# 14_CPU_2.net
KiCad netlist of a schematic drawn in Altium Designer
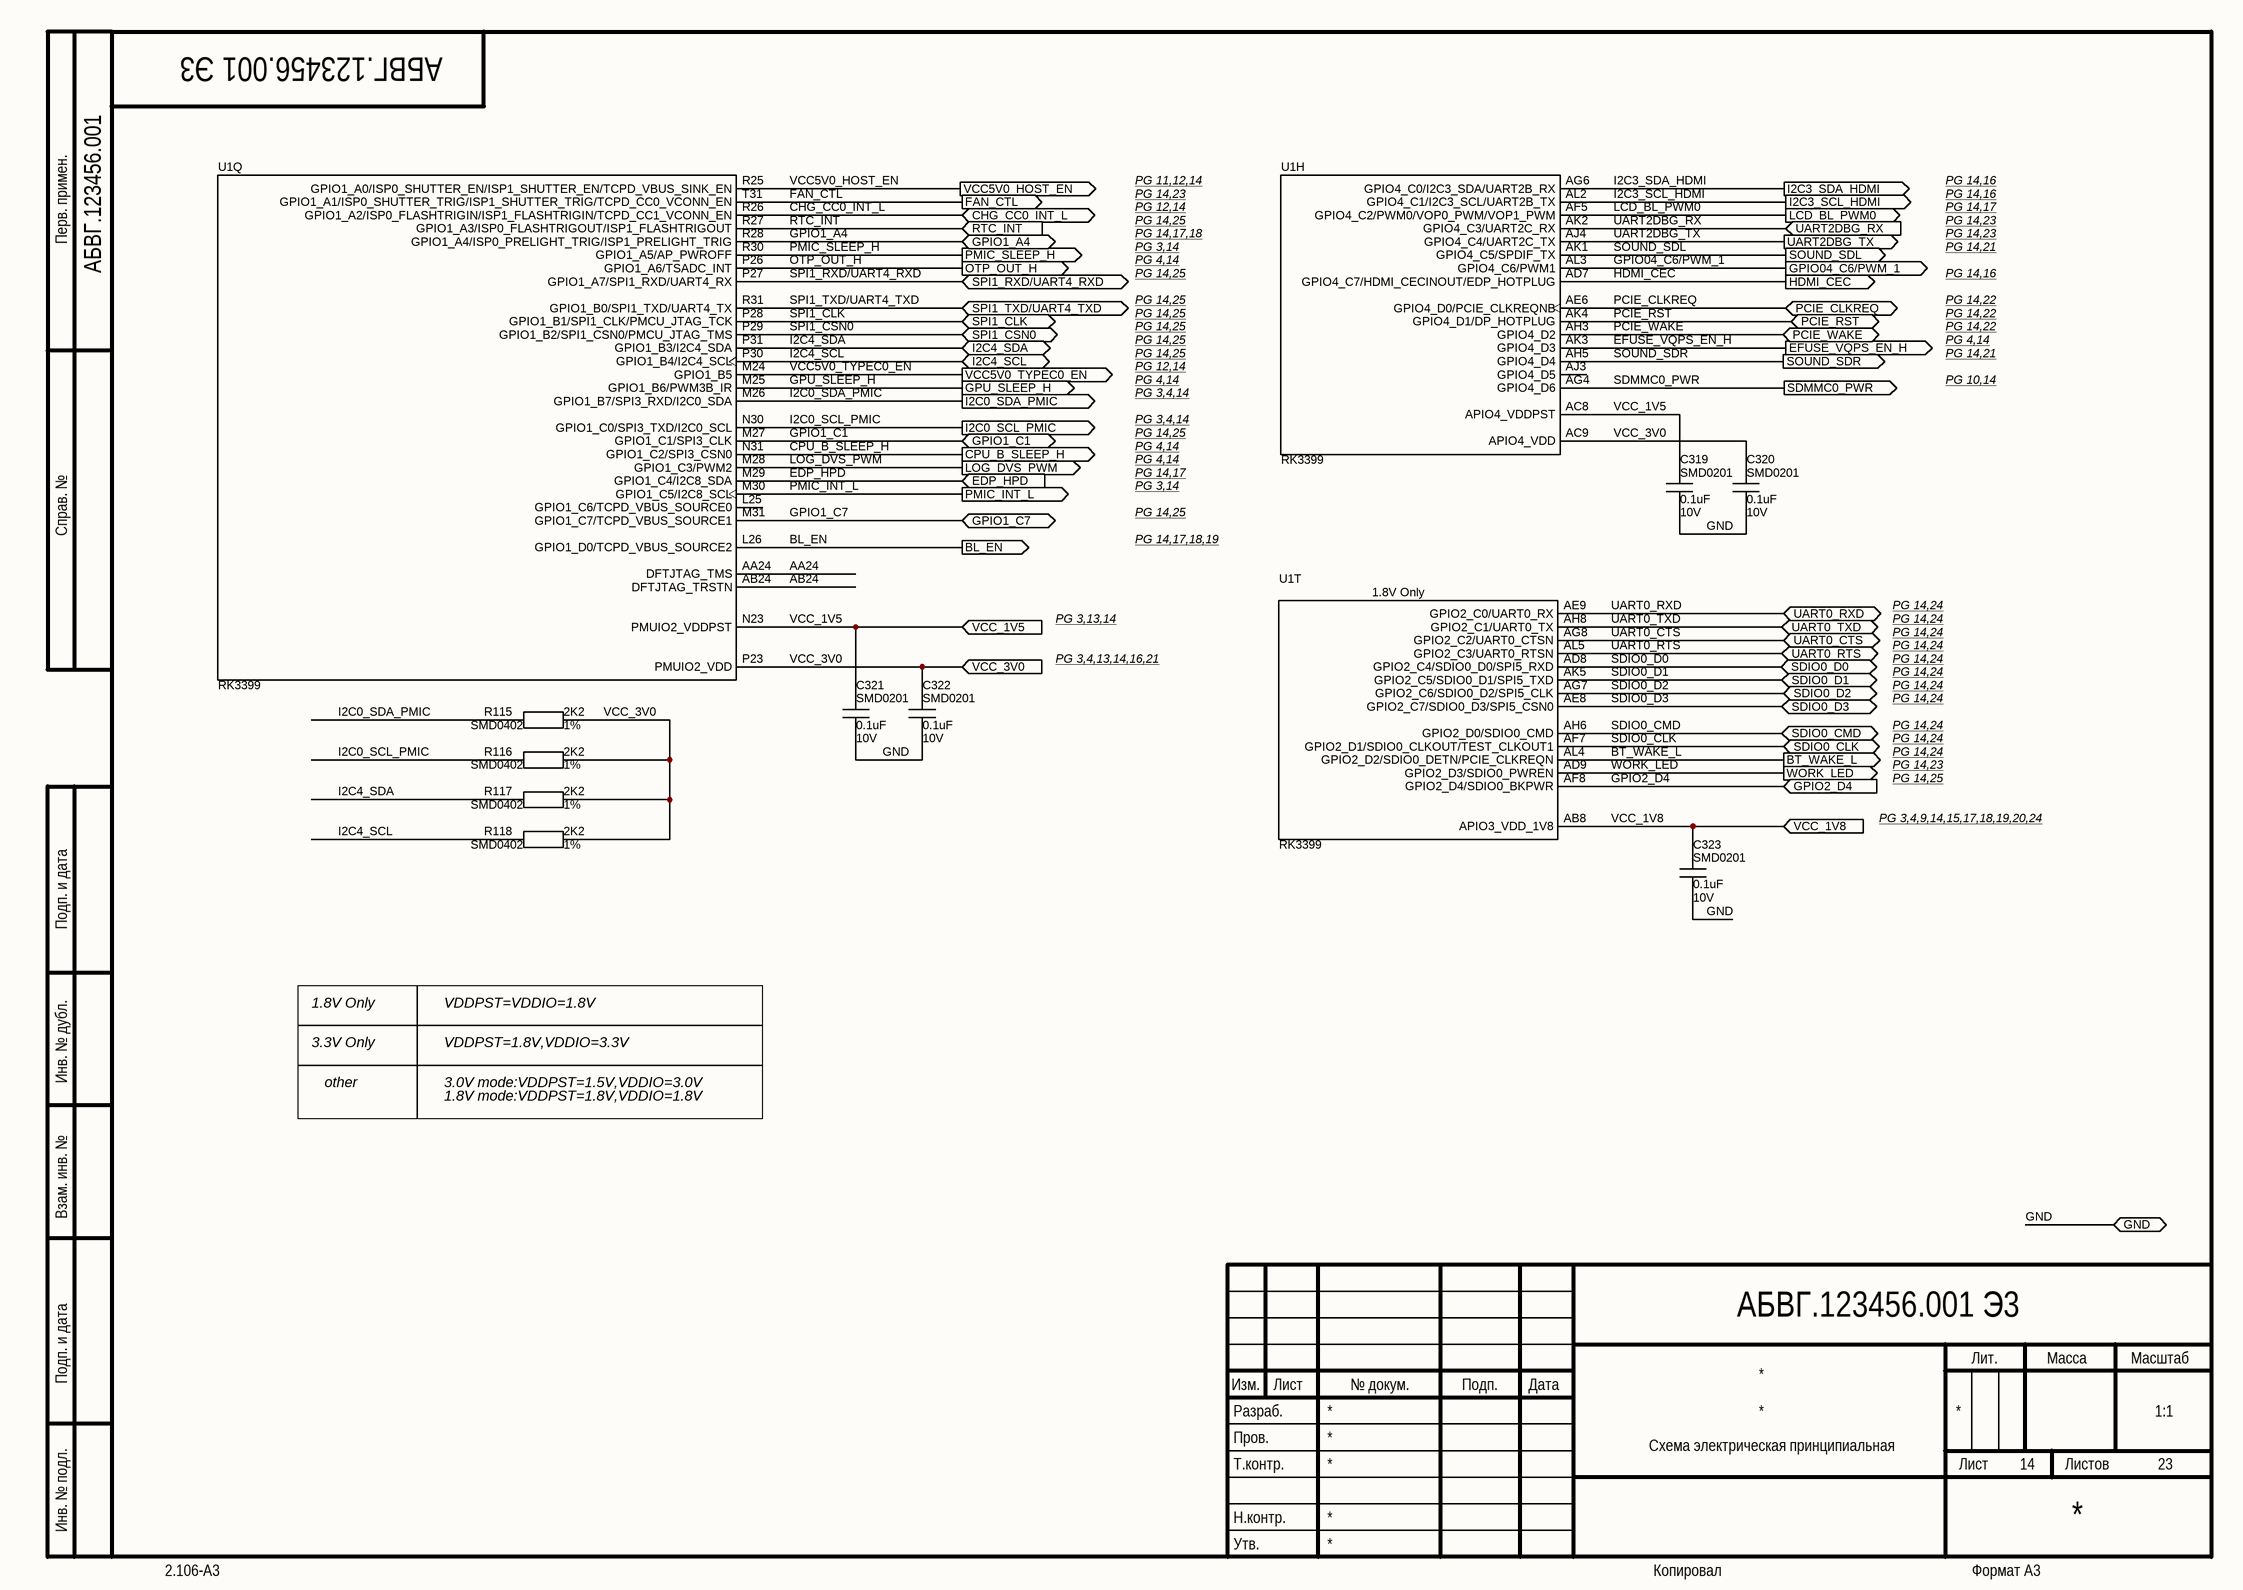
[diagram p0: 14 CPU_2.SchDoc]

(export (version "E")
  (design (tool "Eeschema 10.0.6"))
  (components
    (comp (ref "C319")
      (value "0.1uF")
      (footprint "Didur_PcbLib_1:CAP_SMD_0201")
      (fields
        (field (name "PACKAGE") "SMD0201")
        (field (name "PARTNUMBER") "CC0201KRX5R6BB104")
        (field (name "VOLTAGE") "10V")
      )
      (libsource (lib "Didur_SchLib_1") (part "Ceramic_Cap"))
    )
    (comp (ref "C320")
      (value "0.1uF")
      (footprint "Didur_PcbLib_1:CAP_SMD_0201")
      (fields
        (field (name "PACKAGE") "SMD0201")
        (field (name "PARTNUMBER") "CC0201KRX5R6BB104")
        (field (name "VOLTAGE") "10V")
      )
      (libsource (lib "Didur_SchLib_1") (part "Ceramic_Cap"))
    )
    (comp (ref "C321")
      (value "0.1uF")
      (footprint "Didur_PcbLib_1:CAP_SMD_0201")
      (fields
        (field (name "PACKAGE") "SMD0201")
        (field (name "PARTNUMBER") "CC0201KRX5R6BB104")
        (field (name "VOLTAGE") "10V")
      )
      (libsource (lib "Didur_SchLib_1") (part "Ceramic_Cap"))
    )
    (comp (ref "C322")
      (value "0.1uF")
      (footprint "Didur_PcbLib_1:CAP_SMD_0201")
      (fields
        (field (name "PACKAGE") "SMD0201")
        (field (name "PARTNUMBER") "CC0201KRX5R6BB104")
        (field (name "VOLTAGE") "10V")
      )
      (libsource (lib "Didur_SchLib_1") (part "Ceramic_Cap"))
    )
    (comp (ref "C323")
      (value "0.1uF")
      (footprint "Didur_PcbLib_1:CAP_SMD_0201")
      (fields
        (field (name "PACKAGE") "SMD0201")
        (field (name "PARTNUMBER") "CC0201KRX5R6BB104")
        (field (name "VOLTAGE") "10V")
      )
      (libsource (lib "Didur_SchLib_1") (part "Ceramic_Cap"))
    )
    (comp (ref "R115")
      (value "2K2")
      (footprint "Didur_PcbLib_1:RES_SMD_0402")
      (fields
        (field (name "PACKAGE") "SMD0402")
        (field (name "PARTNUMBER") "RC0402FR-072K2L")
        (field (name "TOLERANCE") "1%")
      )
      (libsource (lib "Didur_SchLib_1") (part "Chip_Res"))
    )
    (comp (ref "R116")
      (value "2K2")
      (footprint "Didur_PcbLib_1:RES_SMD_0402")
      (fields
        (field (name "PACKAGE") "SMD0402")
        (field (name "PARTNUMBER") "RC0402FR-072K2L")
        (field (name "TOLERANCE") "1%")
      )
      (libsource (lib "Didur_SchLib_1") (part "Chip_Res"))
    )
    (comp (ref "R117")
      (value "2K2")
      (footprint "Didur_PcbLib_1:RES_SMD_0402")
      (fields
        (field (name "PACKAGE") "SMD0402")
        (field (name "PARTNUMBER") "RC0402FR-072K2L")
        (field (name "TOLERANCE") "1%")
      )
      (libsource (lib "Didur_SchLib_1") (part "Chip_Res"))
    )
    (comp (ref "R118")
      (value "2K2")
      (footprint "Didur_PcbLib_1:RES_SMD_0402")
      (fields
        (field (name "PACKAGE") "SMD0402")
        (field (name "PARTNUMBER") "RC0402FR-072K2L")
        (field (name "TOLERANCE") "1%")
      )
      (libsource (lib "Didur_SchLib_1") (part "Chip_Res"))
    )
    (comp (ref "U1")
      (value "RK3399")
      (footprint "BGA828C65P31X31_2100X2100X161N")
      (fields (field (name "Comment") "RK3399_FF"))
      (libsource (lib "Didur_SchLib_1") (part "RK3399_FF"))
    )
  )
  (nets
    (net (code "1") (name "/AA24") (class "Default")
      (node (ref "U1") (pin "AA24") (pinfunction "DFTJTAG_TMS_AA24") (pintype "passive"))
    )
    (net (code "2") (name "/AB24") (class "Default")
      (node (ref "U1") (pin "AB24") (pinfunction "DFTJTAG_TRSTN_AB24") (pintype "passive"))
    )
    (net (code "3") (name "/BL_EN") (class "Default")
      (node (ref "U1") (pin "L26") (pinfunction "GPIO1_D0/TCPD_VBUS_SOURCE2_L26") (pintype "passive"))
    )
    (net (code "4") (name "/BT_WAKE_L") (class "Default")
      (node (ref "U1") (pin "AL4") (pinfunction "GPIO2_D2/SDIO0_DETN/PCIE_CLKREQN_AL4") (pintype "passive"))
    )
    (net (code "5") (name "/CHG_CC0_INT_L") (class "Default")
      (node (ref "U1") (pin "R26") (pinfunction "GPIO1_A2/ISP0_FLASHTRIGIN/ISP1_FLASHTRIGIN/TCPD_CC1_VCONN_EN_R26") (pintype "passive"))
    )
    (net (code "6") (name "/CPU_B_SLEEP_H") (class "Default")
      (node (ref "U1") (pin "N31") (pinfunction "GPIO1_C2/SPI3_CSN0_N31") (pintype "passive"))
    )
    (net (code "7") (name "/EDP_HPD") (class "Default")
      (node (ref "U1") (pin "M29") (pinfunction "GPIO1_C4/I2C8_SDA_M29") (pintype "passive"))
    )
    (net (code "8") (name "/EFUSE_VQPS_EN_H") (class "Default")
      (node (ref "U1") (pin "AK3") (pinfunction "GPIO4_D3_AK3") (pintype "passive"))
    )
    (net (code "9") (name "/FAN_CTL") (class "Default")
      (node (ref "U1") (pin "T31") (pinfunction "GPIO1_A1/ISP0_SHUTTER_TRIG/ISP1_SHUTTER_TRIG/TCPD_CC0_VCONN_EN_T31") (pintype "passive"))
    )
    (net (code "10") (name "/GND") (class "Default")
      (node (ref "C319") (pin "2") (pinfunction "2_2") (pintype "power_in"))
      (node (ref "C320") (pin "2") (pinfunction "2_2") (pintype "power_in"))
      (node (ref "C321") (pin "2") (pinfunction "2_2") (pintype "power_in"))
      (node (ref "C322") (pin "2") (pinfunction "2_2") (pintype "power_in"))
      (node (ref "C323") (pin "2") (pinfunction "2_2") (pintype "power_in"))
    )
    (net (code "11") (name "/GPIO1_A4") (class "Default")
      (node (ref "U1") (pin "R28") (pinfunction "GPIO1_A4/ISP0_PRELIGHT_TRIG/ISP1_PRELIGHT_TRIG_R28") (pintype "passive"))
    )
    (net (code "12") (name "/GPIO1_C1") (class "Default")
      (node (ref "U1") (pin "M27") (pinfunction "GPIO1_C1/SPI3_CLK_M27") (pintype "passive"))
    )
    (net (code "13") (name "/GPIO1_C7") (class "Default")
      (node (ref "U1") (pin "M31") (pinfunction "GPIO1_C7/TCPD_VBUS_SOURCE1_M31") (pintype "passive"))
    )
    (net (code "14") (name "/GPIO2_D4") (class "Default")
      (node (ref "U1") (pin "AF8") (pinfunction "GPIO2_D4/SDIO0_BKPWR_AF8") (pintype "passive"))
    )
    (net (code "15") (name "/GPIO04_C6{slash}PWM_1") (class "Default")
      (node (ref "U1") (pin "AL3") (pinfunction "GPIO4_C6/PWM1_AL3") (pintype "passive"))
    )
    (net (code "16") (name "/GPU_SLEEP_H") (class "Default")
      (node (ref "U1") (pin "M25") (pinfunction "GPIO1_B6/PWM3B_IR_M25") (pintype "passive"))
    )
    (net (code "17") (name "/HDMI_CEC") (class "Default")
      (node (ref "U1") (pin "AD7") (pinfunction "GPIO4_C7/HDMI_CECINOUT/EDP_HOTPLUG_AD7") (pintype "passive"))
    )
    (net (code "18") (name "/I2C0_SCL_PMIC") (class "Default")
      (node (ref "R116") (pin "2") (pinfunction "2_2") (pintype "passive"))
      (node (ref "U1") (pin "N30") (pinfunction "GPIO1_C0/SPI3_TXD/I2C0_SCL_N30") (pintype "passive"))
    )
    (net (code "19") (name "/I2C0_SDA_PMIC") (class "Default")
      (node (ref "R115") (pin "2") (pinfunction "2_2") (pintype "passive"))
      (node (ref "U1") (pin "M26") (pinfunction "GPIO1_B7/SPI3_RXD/I2C0_SDA_M26") (pintype "passive"))
    )
    (net (code "20") (name "/I2C3_SCL_HDMI") (class "Default")
      (node (ref "U1") (pin "AL2") (pinfunction "GPIO4_C1/I2C3_SCL/UART2B_TX_AL2") (pintype "passive"))
    )
    (net (code "21") (name "/I2C3_SDA_HDMI") (class "Default")
      (node (ref "U1") (pin "AG6") (pinfunction "GPIO4_C0/I2C3_SDA/UART2B_RX_AG6") (pintype "passive"))
    )
    (net (code "22") (name "/I2C4_SCL") (class "Default")
      (node (ref "R118") (pin "2") (pinfunction "2_2") (pintype "passive"))
      (node (ref "U1") (pin "P30") (pinfunction "GPIO1_B4/I2C4_SCL_P30") (pintype "passive"))
    )
    (net (code "23") (name "/I2C4_SDA") (class "Default")
      (node (ref "R117") (pin "2") (pinfunction "2_2") (pintype "passive"))
      (node (ref "U1") (pin "P31") (pinfunction "GPIO1_B3/I2C4_SDA_P31") (pintype "passive"))
    )
    (net (code "24") (name "/LCD_BL_PWM0") (class "Default")
      (node (ref "U1") (pin "AF5") (pinfunction "GPIO4_C2/PWM0/VOP0_PWM/VOP1_PWM_AF5") (pintype "passive"))
    )
    (net (code "25") (name "/LOG_DVS_PWM") (class "Default")
      (node (ref "U1") (pin "M28") (pinfunction "GPIO1_C3/PWM2_M28") (pintype "passive"))
    )
    (net (code "26") (name "/OTP_OUT_H") (class "Default")
      (node (ref "U1") (pin "P26") (pinfunction "GPIO1_A6/TSADC_INT_P26") (pintype "passive"))
    )
    (net (code "27") (name "/PCIE_CLKREQ") (class "Default")
      (node (ref "U1") (pin "AE6") (pinfunction "GPIO4_D0/PCIE_CLKREQNB_AE6") (pintype "passive"))
    )
    (net (code "28") (name "/PCIE_RST") (class "Default")
      (node (ref "U1") (pin "AK4") (pinfunction "GPIO4_D1/DP_HOTPLUG_AK4") (pintype "passive"))
    )
    (net (code "29") (name "/PCIE_WAKE") (class "Default")
      (node (ref "U1") (pin "AH3") (pinfunction "GPIO4_D2_AH3") (pintype "passive"))
    )
    (net (code "30") (name "/PMIC_INT_L") (class "Default")
      (node (ref "U1") (pin "M30") (pinfunction "GPIO1_C5/I2C8_SCL_M30") (pintype "passive"))
    )
    (net (code "31") (name "/PMIC_SLEEP_H") (class "Default")
      (node (ref "U1") (pin "R30") (pinfunction "GPIO1_A5/AP_PWROFF_R30") (pintype "passive"))
    )
    (net (code "32") (name "/RTC_INT") (class "Default")
      (node (ref "U1") (pin "R27") (pinfunction "GPIO1_A3/ISP0_FLASHTRIGOUT/ISP1_FLASHTRIGOUT_R27") (pintype "passive"))
    )
    (net (code "33") (name "/SDIO0_CLK") (class "Default")
      (node (ref "U1") (pin "AF7") (pinfunction "GPIO2_D1/SDIO0_CLKOUT/TEST_CLKOUT1_AF7") (pintype "passive"))
    )
    (net (code "34") (name "/SDIO0_CMD") (class "Default")
      (node (ref "U1") (pin "AH6") (pinfunction "GPIO2_D0/SDIO0_CMD_AH6") (pintype "passive"))
    )
    (net (code "35") (name "/SDIO0_D0") (class "Default")
      (node (ref "U1") (pin "AD8") (pinfunction "GPIO2_C4/SDIO0_D0/SPI5_RXD_AD8") (pintype "passive"))
    )
    (net (code "36") (name "/SDIO0_D1") (class "Default")
      (node (ref "U1") (pin "AK5") (pinfunction "GPIO2_C5/SDIO0_D1/SPI5_TXD_AK5") (pintype "passive"))
    )
    (net (code "37") (name "/SDIO0_D2") (class "Default")
      (node (ref "U1") (pin "AG7") (pinfunction "GPIO2_C6/SDIO0_D2/SPI5_CLK_AG7") (pintype "passive"))
    )
    (net (code "38") (name "/SDIO0_D3") (class "Default")
      (node (ref "U1") (pin "AE8") (pinfunction "GPIO2_C7/SDIO0_D3/SPI5_CSN0_AE8") (pintype "passive"))
    )
    (net (code "39") (name "/SDMMC0_PWR") (class "Default")
      (node (ref "U1") (pin "AG4") (pinfunction "GPIO4_D6_AG4") (pintype "passive"))
    )
    (net (code "40") (name "/SOUND_SDL") (class "Default")
      (node (ref "U1") (pin "AK1") (pinfunction "GPIO4_C5/SPDIF_TX_AK1") (pintype "passive"))
    )
    (net (code "41") (name "/SOUND_SDR") (class "Default")
      (node (ref "U1") (pin "AH5") (pinfunction "GPIO4_D4_AH5") (pintype "passive"))
    )
    (net (code "42") (name "/SPI1_CLK") (class "Default")
      (node (ref "U1") (pin "P28") (pinfunction "GPIO1_B1/SPI1_CLK/PMCU_JTAG_TCK_P28") (pintype "passive"))
    )
    (net (code "43") (name "/SPI1_CSN0") (class "Default")
      (node (ref "U1") (pin "P29") (pinfunction "GPIO1_B2/SPI1_CSN0/PMCU_JTAG_TMS_P29") (pintype "passive"))
    )
    (net (code "44") (name "/SPI1_RXD{slash}UART4_RXD") (class "Default")
      (node (ref "U1") (pin "P27") (pinfunction "GPIO1_A7/SPI1_RXD/UART4_RX_P27") (pintype "passive"))
    )
    (net (code "45") (name "/SPI1_TXD{slash}UART4_TXD") (class "Default")
      (node (ref "U1") (pin "R31") (pinfunction "GPIO1_B0/SPI1_TXD/UART4_TX_R31") (pintype "passive"))
    )
    (net (code "46") (name "/UART0_CTS") (class "Default")
      (node (ref "U1") (pin "AG8") (pinfunction "GPIO2_C2/UART0_CTSN_AG8") (pintype "passive"))
    )
    (net (code "47") (name "/UART0_RTS") (class "Default")
      (node (ref "U1") (pin "AL5") (pinfunction "GPIO2_C3/UART0_RTSN_AL5") (pintype "passive"))
    )
    (net (code "48") (name "/UART0_RXD") (class "Default")
      (node (ref "U1") (pin "AE9") (pinfunction "GPIO2_C0/UART0_RX_AE9") (pintype "passive"))
    )
    (net (code "49") (name "/UART0_TXD") (class "Default")
      (node (ref "U1") (pin "AH8") (pinfunction "GPIO2_C1/UART0_TX_AH8") (pintype "passive"))
    )
    (net (code "50") (name "/UART2DBG_RX") (class "Default")
      (node (ref "U1") (pin "AK2") (pinfunction "GPIO4_C3/UART2C_RX_AK2") (pintype "passive"))
    )
    (net (code "51") (name "/UART2DBG_TX") (class "Default")
      (node (ref "U1") (pin "AJ4") (pinfunction "GPIO4_C4/UART2C_TX_AJ4") (pintype "passive"))
    )
    (net (code "52") (name "/VCC5V0_HOST_EN") (class "Default")
      (node (ref "U1") (pin "R25") (pinfunction "GPIO1_A0/ISP0_SHUTTER_EN/ISP1_SHUTTER_EN/TCPD_VBUS_SINK_EN_R25") (pintype "passive"))
    )
    (net (code "53") (name "/VCC5V0_TYPEC0_EN") (class "Default")
      (node (ref "U1") (pin "M24") (pinfunction "GPIO1_B5_M24") (pintype "passive"))
    )
    (net (code "54") (name "/VCC_1V5") (class "Default")
      (node (ref "C319") (pin "1") (pinfunction "1_1") (pintype "power_in"))
      (node (ref "C321") (pin "1") (pinfunction "1_1") (pintype "power_in"))
      (node (ref "U1") (pin "AC8") (pinfunction "APIO4_VDDPST_AC8") (pintype "passive"))
      (node (ref "U1") (pin "N23") (pinfunction "PMUIO2_VDDPST_N23") (pintype "passive"))
    )
    (net (code "55") (name "/VCC_1V8") (class "Default")
      (node (ref "C323") (pin "1") (pinfunction "1_1") (pintype "power_in"))
      (node (ref "U1") (pin "AB8") (pinfunction "APIO3_VDD_1V8_AB8") (pintype "passive"))
    )
    (net (code "56") (name "/VCC_3V0") (class "Default")
      (node (ref "C320") (pin "1") (pinfunction "1_1") (pintype "power_in"))
      (node (ref "C322") (pin "1") (pinfunction "1_1") (pintype "power_in"))
      (node (ref "R115") (pin "1") (pinfunction "1_1") (pintype "passive"))
      (node (ref "R116") (pin "1") (pinfunction "1_1") (pintype "passive"))
      (node (ref "R117") (pin "1") (pinfunction "1_1") (pintype "passive"))
      (node (ref "R118") (pin "1") (pinfunction "1_1") (pintype "passive"))
      (node (ref "U1") (pin "AC9") (pinfunction "APIO4_VDD_AC9") (pintype "passive"))
      (node (ref "U1") (pin "P23") (pinfunction "PMUIO2_VDD_P23") (pintype "passive"))
    )
    (net (code "57") (name "/WORK_LED") (class "Default")
      (node (ref "U1") (pin "AD9") (pinfunction "GPIO2_D3/SDIO0_PWREN_AD9") (pintype "passive"))
    )
    (net (code "58") (name "unconnected-(U1H-GPIO4_D5-PadAJ3)") (class "Default")
      (node (ref "U1") (pin "AJ3") (pinfunction "GPIO4_D5_AJ3") (pintype "passive"))
    )
    (net (code "59") (name "unconnected-(U1Q-GPIO1_C6{slash}TCPD_VBUS_SOURCE0-PadL25)") (class "Default")
      (node (ref "U1") (pin "L25") (pinfunction "GPIO1_C6/TCPD_VBUS_SOURCE0_L25") (pintype "passive"))
    )
  )
)
